# untitled.net
KiCad netlist of a schematic drawn in EAGLE
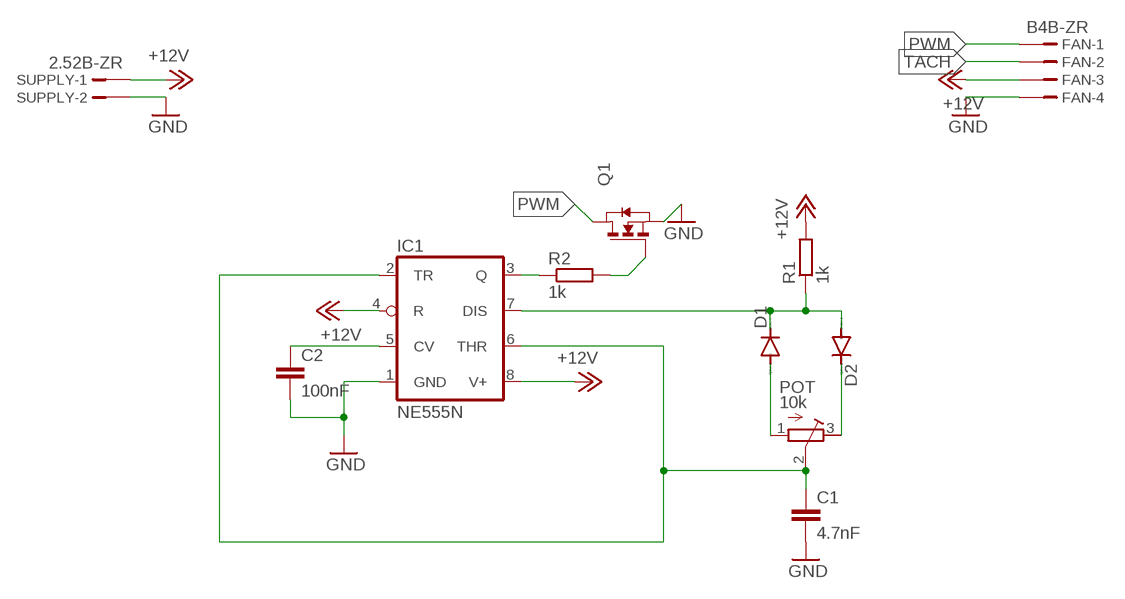
[diagram p0: schematic, sheet 1]

(export (version "E")
  (design (tool "Eeschema 10.0.6"))
  (components
    (comp (ref "C1")
      (value "4.7nF")
      (footprint "eagle-import:C050-030X075")
      (libsource (lib "eagle-import") (part "C-EU050-030X075"))
    )
    (comp (ref "C2")
      (value "100nF")
      (footprint "eagle-import:C025-025X050")
      (libsource (lib "eagle-import") (part "C-EU025-025X050"))
    )
    (comp (ref "D1")
      (value "CGRM4001-G")
      (footprint "eagle-import:SOD-123_MINI-SMA")
      (libsource (lib "eagle-import") (part "CGRM400-G1"))
    )
    (comp (ref "D2")
      (value "CGRM4001-G")
      (footprint "eagle-import:SOD-123_MINI-SMA")
      (libsource (lib "eagle-import") (part "CGRM400-G1"))
    )
    (comp (ref "FAN")
      (value "B4B-ZR")
      (footprint "eagle-import:B4B-ZR")
      (fields (field (name "MF") "FARNELL") (field (name "MPN") "B4B-ZR(LF)(SN)"))
      (libsource (lib "eagle-import") (part "?4B-ZRB"))
    )
    (comp (ref "IC1")
      (value "NE555N")
      (footprint "eagle-import:DIL08")
      (libsource (lib "eagle-import") (part "555NNE"))
    )
    (comp (ref "POT")
      (value "10k")
      (footprint "eagle-import:RTRIM3296W")
      (libsource (lib "eagle-import") (part "R-TRIMM3296W"))
    )
    (comp (ref "Q1")
      (value "NMOSSOT23")
      (footprint "eagle-import:SOT-23")
      (libsource (lib "eagle-import") (part "NMOSSOT23"))
    )
    (comp (ref "R1")
      (value "1k")
      (footprint "eagle-import:R0603")
      (libsource (lib "eagle-import") (part "R-EU_R0603"))
    )
    (comp (ref "R2")
      (value "1k")
      (footprint "eagle-import:R0603")
      (libsource (lib "eagle-import") (part "R-EU_R0603"))
    )
    (comp (ref "SUPPLY")
      (value "2.52B-ZR")
      (footprint "eagle-import:B2B-ZR2.5")
      (libsource (lib "eagle-import") (part "?2B-ZR2.5"))
    )
  )
  (nets
    (net (code "1") (name "+12V") (class "Default")
      (node (ref "FAN") (pin "3") (pinfunction "1_3") (pintype "passive"))
      (node (ref "IC1") (pin "4") (pinfunction "R_4") (pintype "input"))
      (node (ref "IC1") (pin "8") (pinfunction "V+_8") (pintype "power_in"))
      (node (ref "R1") (pin "2") (pinfunction "2_2") (pintype "passive"))
      (node (ref "SUPPLY") (pin "1") (pinfunction "1_1") (pintype "passive"))
    )
    (net (code "2") (name "GND") (class "Default")
      (node (ref "C1") (pin "2") (pinfunction "2_2") (pintype "passive"))
      (node (ref "C2") (pin "2") (pinfunction "2_2") (pintype "passive"))
      (node (ref "FAN") (pin "4") (pinfunction "1_4") (pintype "passive"))
      (node (ref "IC1") (pin "1") (pinfunction "GND_1") (pintype "power_in"))
      (node (ref "Q1") (pin "2") (pinfunction "S_2") (pintype "passive"))
      (node (ref "SUPPLY") (pin "2") (pinfunction "1_2") (pintype "passive"))
    )
    (net (code "3") (name "Net-(IC1-CV)") (class "Default")
      (node (ref "C2") (pin "1") (pinfunction "1_1") (pintype "passive"))
      (node (ref "IC1") (pin "5") (pinfunction "CV_5") (pintype "input"))
    )
    (net (code "4") (name "Net-(IC1-DIS)") (class "Default")
      (node (ref "D1") (pin "C") (pinfunction "C_C") (pintype "passive"))
      (node (ref "D2") (pin "A") (pinfunction "A_A") (pintype "passive"))
      (node (ref "IC1") (pin "7") (pinfunction "DIS_7") (pintype "input"))
      (node (ref "R1") (pin "1") (pinfunction "1_1") (pintype "passive"))
    )
    (net (code "5") (name "Net-(IC1-Q)") (class "Default")
      (node (ref "IC1") (pin "3") (pinfunction "Q_3") (pintype "output"))
      (node (ref "R2") (pin "1") (pinfunction "1_1") (pintype "passive"))
    )
    (net (code "6") (name "Net-(IC1-THR)") (class "Default")
      (node (ref "C1") (pin "1") (pinfunction "1_1") (pintype "passive"))
      (node (ref "IC1") (pin "2") (pinfunction "TR_2") (pintype "input"))
      (node (ref "IC1") (pin "6") (pinfunction "THR_6") (pintype "input"))
      (node (ref "POT") (pin "2") (pinfunction "S_2") (pintype "passive"))
    )
    (net (code "7") (name "Net-(POT-A)") (class "Default")
      (node (ref "D1") (pin "A") (pinfunction "A_A") (pintype "passive"))
      (node (ref "POT") (pin "1") (pinfunction "A_1") (pintype "passive"))
    )
    (net (code "8") (name "Net-(POT-E)") (class "Default")
      (node (ref "D2") (pin "C") (pinfunction "C_C") (pintype "passive"))
      (node (ref "POT") (pin "3") (pinfunction "E_3") (pintype "passive"))
    )
    (net (code "9") (name "Net-(Q1-G)") (class "Default")
      (node (ref "Q1") (pin "3") (pinfunction "G_3") (pintype "passive"))
      (node (ref "R2") (pin "2") (pinfunction "2_2") (pintype "passive"))
    )
    (net (code "10") (name "PWM") (class "Default")
      (node (ref "FAN") (pin "1") (pinfunction "1_1") (pintype "passive"))
      (node (ref "Q1") (pin "1") (pinfunction "D_1") (pintype "passive"))
    )
    (net (code "11") (name "TACH") (class "Default")
      (node (ref "FAN") (pin "2") (pinfunction "1_2") (pintype "passive"))
    )
  )
)
